# brakelight.net
KiCad netlist of a schematic drawn in EAGLE
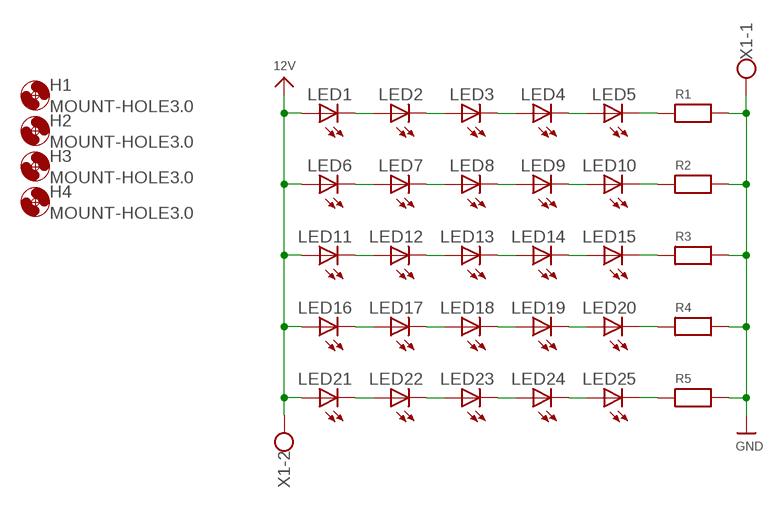
[diagram p0: schematic, sheet 1]

(export (version "E")
  (design (tool "Eeschema 10.0.6"))
  (components
    (comp (ref "H1")
      (value "MOUNT-HOLE3.0")
      (footprint "eagle-import:3,0")
      (libsource (lib "eagle-import") (part "MOUNT-HOLE3.0"))
    )
    (comp (ref "H2")
      (value "MOUNT-HOLE3.0")
      (footprint "eagle-import:3,0")
      (libsource (lib "eagle-import") (part "MOUNT-HOLE3.0"))
    )
    (comp (ref "H3")
      (value "MOUNT-HOLE3.0")
      (footprint "eagle-import:3,0")
      (libsource (lib "eagle-import") (part "MOUNT-HOLE3.0"))
    )
    (comp (ref "H4")
      (value "MOUNT-HOLE3.0")
      (footprint "eagle-import:3,0")
      (libsource (lib "eagle-import") (part "MOUNT-HOLE3.0"))
    )
    (comp (ref "LED1")
      (value "LEDP-LCC-2")
      (footprint "eagle-import:P-LCC-2")
      (libsource (lib "eagle-import") (part "LEDP-LCC-2"))
    )
    (comp (ref "LED2")
      (value "LEDP-LCC-2")
      (footprint "eagle-import:P-LCC-2")
      (libsource (lib "eagle-import") (part "LEDP-LCC-2"))
    )
    (comp (ref "LED3")
      (value "LEDP-LCC-2")
      (footprint "eagle-import:P-LCC-2")
      (libsource (lib "eagle-import") (part "LEDP-LCC-2"))
    )
    (comp (ref "LED4")
      (value "LEDP-LCC-2")
      (footprint "eagle-import:P-LCC-2")
      (libsource (lib "eagle-import") (part "LEDP-LCC-2"))
    )
    (comp (ref "LED5")
      (value "LEDP-LCC-2")
      (footprint "eagle-import:P-LCC-2")
      (libsource (lib "eagle-import") (part "LEDP-LCC-2"))
    )
    (comp (ref "LED6")
      (value "LEDP-LCC-2")
      (footprint "eagle-import:P-LCC-2")
      (libsource (lib "eagle-import") (part "LEDP-LCC-2"))
    )
    (comp (ref "LED7")
      (value "LEDP-LCC-2")
      (footprint "eagle-import:P-LCC-2")
      (libsource (lib "eagle-import") (part "LEDP-LCC-2"))
    )
    (comp (ref "LED8")
      (value "LEDP-LCC-2")
      (footprint "eagle-import:P-LCC-2")
      (libsource (lib "eagle-import") (part "LEDP-LCC-2"))
    )
    (comp (ref "LED9")
      (value "LEDP-LCC-2")
      (footprint "eagle-import:P-LCC-2")
      (libsource (lib "eagle-import") (part "LEDP-LCC-2"))
    )
    (comp (ref "LED10")
      (value "LEDP-LCC-2")
      (footprint "eagle-import:P-LCC-2")
      (libsource (lib "eagle-import") (part "LEDP-LCC-2"))
    )
    (comp (ref "LED11")
      (value "LEDP-LCC-2")
      (footprint "eagle-import:P-LCC-2")
      (libsource (lib "eagle-import") (part "LEDP-LCC-2"))
    )
    (comp (ref "LED12")
      (value "LEDP-LCC-2")
      (footprint "eagle-import:P-LCC-2")
      (libsource (lib "eagle-import") (part "LEDP-LCC-2"))
    )
    (comp (ref "LED13")
      (value "LEDP-LCC-2")
      (footprint "eagle-import:P-LCC-2")
      (libsource (lib "eagle-import") (part "LEDP-LCC-2"))
    )
    (comp (ref "LED14")
      (value "LEDP-LCC-2")
      (footprint "eagle-import:P-LCC-2")
      (libsource (lib "eagle-import") (part "LEDP-LCC-2"))
    )
    (comp (ref "LED15")
      (value "LEDP-LCC-2")
      (footprint "eagle-import:P-LCC-2")
      (libsource (lib "eagle-import") (part "LEDP-LCC-2"))
    )
    (comp (ref "LED16")
      (value "LEDP-LCC-2")
      (footprint "eagle-import:P-LCC-2")
      (libsource (lib "eagle-import") (part "LEDP-LCC-2"))
    )
    (comp (ref "LED17")
      (value "LEDP-LCC-2")
      (footprint "eagle-import:P-LCC-2")
      (libsource (lib "eagle-import") (part "LEDP-LCC-2"))
    )
    (comp (ref "LED18")
      (value "LEDP-LCC-2")
      (footprint "eagle-import:P-LCC-2")
      (libsource (lib "eagle-import") (part "LEDP-LCC-2"))
    )
    (comp (ref "LED19")
      (value "LEDP-LCC-2")
      (footprint "eagle-import:P-LCC-2")
      (libsource (lib "eagle-import") (part "LEDP-LCC-2"))
    )
    (comp (ref "LED20")
      (value "LEDP-LCC-2")
      (footprint "eagle-import:P-LCC-2")
      (libsource (lib "eagle-import") (part "LEDP-LCC-2"))
    )
    (comp (ref "LED21")
      (value "LEDP-LCC-2")
      (footprint "eagle-import:P-LCC-2")
      (libsource (lib "eagle-import") (part "LEDP-LCC-2"))
    )
    (comp (ref "LED22")
      (value "LEDP-LCC-2")
      (footprint "eagle-import:P-LCC-2")
      (libsource (lib "eagle-import") (part "LEDP-LCC-2"))
    )
    (comp (ref "LED23")
      (value "LEDP-LCC-2")
      (footprint "eagle-import:P-LCC-2")
      (libsource (lib "eagle-import") (part "LEDP-LCC-2"))
    )
    (comp (ref "LED24")
      (value "LEDP-LCC-2")
      (footprint "eagle-import:P-LCC-2")
      (libsource (lib "eagle-import") (part "LEDP-LCC-2"))
    )
    (comp (ref "LED25")
      (value "LEDP-LCC-2")
      (footprint "eagle-import:P-LCC-2")
      (libsource (lib "eagle-import") (part "LEDP-LCC-2"))
    )
    (comp (ref "R1")
      (value "RESISTOR0805")
      (footprint "eagle-import:0805")
      (libsource (lib "eagle-import") (part "RESISTOR0805"))
    )
    (comp (ref "R2")
      (value "RESISTOR0805")
      (footprint "eagle-import:0805")
      (libsource (lib "eagle-import") (part "RESISTOR0805"))
    )
    (comp (ref "R3")
      (value "RESISTOR0805")
      (footprint "eagle-import:0805")
      (libsource (lib "eagle-import") (part "RESISTOR0805"))
    )
    (comp (ref "R4")
      (value "RESISTOR0805")
      (footprint "eagle-import:0805")
      (libsource (lib "eagle-import") (part "RESISTOR0805"))
    )
    (comp (ref "R5")
      (value "RESISTOR0805")
      (footprint "eagle-import:0805")
      (libsource (lib "eagle-import") (part "RESISTOR0805"))
    )
    (comp (ref "X1")
      (value "W237-102")
      (footprint "eagle-import:W237-102")
      (fields (field (name "MPN") "237-102"))
      (libsource (lib "eagle-import") (part "W237-102"))
    )
  )
  (nets
    (net (code "1") (name "12V") (class "Default")
      (node (ref "LED1") (pin "A") (pinfunction "A_A") (pintype "passive"))
      (node (ref "LED11") (pin "A") (pinfunction "A_A") (pintype "passive"))
      (node (ref "LED16") (pin "A") (pinfunction "A_A") (pintype "passive"))
      (node (ref "LED21") (pin "A") (pinfunction "A_A") (pintype "passive"))
      (node (ref "LED6") (pin "A") (pinfunction "A_A") (pintype "passive"))
      (node (ref "X1") (pin "2") (pinfunction "KL_2") (pintype "passive"))
    )
    (net (code "2") (name "GND") (class "Default")
      (node (ref "R1") (pin "2") (pinfunction "2_2") (pintype "passive"))
      (node (ref "R2") (pin "2") (pinfunction "2_2") (pintype "passive"))
      (node (ref "R3") (pin "2") (pinfunction "2_2") (pintype "passive"))
      (node (ref "R4") (pin "2") (pinfunction "2_2") (pintype "passive"))
      (node (ref "R5") (pin "2") (pinfunction "2_2") (pintype "passive"))
      (node (ref "X1") (pin "1") (pinfunction "KL_1") (pintype "passive"))
    )
    (net (code "3") (name "Net-(LED1-PadC)") (class "Default")
      (node (ref "LED1") (pin "C") (pinfunction "C_C") (pintype "passive"))
      (node (ref "LED2") (pin "A") (pinfunction "A_A") (pintype "passive"))
    )
    (net (code "4") (name "Net-(LED2-PadC)") (class "Default")
      (node (ref "LED2") (pin "C") (pinfunction "C_C") (pintype "passive"))
      (node (ref "LED3") (pin "A") (pinfunction "A_A") (pintype "passive"))
    )
    (net (code "5") (name "Net-(LED3-PadC)") (class "Default")
      (node (ref "LED3") (pin "C") (pinfunction "C_C") (pintype "passive"))
      (node (ref "LED4") (pin "A") (pinfunction "A_A") (pintype "passive"))
    )
    (net (code "6") (name "Net-(LED4-PadC)") (class "Default")
      (node (ref "LED4") (pin "C") (pinfunction "C_C") (pintype "passive"))
      (node (ref "LED5") (pin "A") (pinfunction "A_A") (pintype "passive"))
    )
    (net (code "7") (name "Net-(LED5-PadC)") (class "Default")
      (node (ref "LED5") (pin "C") (pinfunction "C_C") (pintype "passive"))
      (node (ref "R1") (pin "1") (pinfunction "1_1") (pintype "passive"))
    )
    (net (code "8") (name "Net-(LED6-PadC)") (class "Default")
      (node (ref "LED6") (pin "C") (pinfunction "C_C") (pintype "passive"))
      (node (ref "LED7") (pin "A") (pinfunction "A_A") (pintype "passive"))
    )
    (net (code "9") (name "Net-(LED7-PadC)") (class "Default")
      (node (ref "LED7") (pin "C") (pinfunction "C_C") (pintype "passive"))
      (node (ref "LED8") (pin "A") (pinfunction "A_A") (pintype "passive"))
    )
    (net (code "10") (name "Net-(LED8-PadC)") (class "Default")
      (node (ref "LED8") (pin "C") (pinfunction "C_C") (pintype "passive"))
      (node (ref "LED9") (pin "A") (pinfunction "A_A") (pintype "passive"))
    )
    (net (code "11") (name "Net-(LED10-PadA)") (class "Default")
      (node (ref "LED10") (pin "A") (pinfunction "A_A") (pintype "passive"))
      (node (ref "LED9") (pin "C") (pinfunction "C_C") (pintype "passive"))
    )
    (net (code "12") (name "Net-(LED10-PadC)") (class "Default")
      (node (ref "LED10") (pin "C") (pinfunction "C_C") (pintype "passive"))
      (node (ref "R2") (pin "1") (pinfunction "1_1") (pintype "passive"))
    )
    (net (code "13") (name "Net-(LED11-PadC)") (class "Default")
      (node (ref "LED11") (pin "C") (pinfunction "C_C") (pintype "passive"))
      (node (ref "LED12") (pin "A") (pinfunction "A_A") (pintype "passive"))
    )
    (net (code "14") (name "Net-(LED12-PadC)") (class "Default")
      (node (ref "LED12") (pin "C") (pinfunction "C_C") (pintype "passive"))
      (node (ref "LED13") (pin "A") (pinfunction "A_A") (pintype "passive"))
    )
    (net (code "15") (name "Net-(LED13-PadC)") (class "Default")
      (node (ref "LED13") (pin "C") (pinfunction "C_C") (pintype "passive"))
      (node (ref "LED14") (pin "A") (pinfunction "A_A") (pintype "passive"))
    )
    (net (code "16") (name "Net-(LED14-PadC)") (class "Default")
      (node (ref "LED14") (pin "C") (pinfunction "C_C") (pintype "passive"))
      (node (ref "LED15") (pin "A") (pinfunction "A_A") (pintype "passive"))
    )
    (net (code "17") (name "Net-(LED15-PadC)") (class "Default")
      (node (ref "LED15") (pin "C") (pinfunction "C_C") (pintype "passive"))
      (node (ref "R3") (pin "1") (pinfunction "1_1") (pintype "passive"))
    )
    (net (code "18") (name "Net-(LED16-PadC)") (class "Default")
      (node (ref "LED16") (pin "C") (pinfunction "C_C") (pintype "passive"))
      (node (ref "LED17") (pin "A") (pinfunction "A_A") (pintype "passive"))
    )
    (net (code "19") (name "Net-(LED17-PadC)") (class "Default")
      (node (ref "LED17") (pin "C") (pinfunction "C_C") (pintype "passive"))
      (node (ref "LED18") (pin "A") (pinfunction "A_A") (pintype "passive"))
    )
    (net (code "20") (name "Net-(LED18-PadC)") (class "Default")
      (node (ref "LED18") (pin "C") (pinfunction "C_C") (pintype "passive"))
      (node (ref "LED19") (pin "A") (pinfunction "A_A") (pintype "passive"))
    )
    (net (code "21") (name "Net-(LED19-PadC)") (class "Default")
      (node (ref "LED19") (pin "C") (pinfunction "C_C") (pintype "passive"))
      (node (ref "LED20") (pin "A") (pinfunction "A_A") (pintype "passive"))
    )
    (net (code "22") (name "Net-(LED20-PadC)") (class "Default")
      (node (ref "LED20") (pin "C") (pinfunction "C_C") (pintype "passive"))
      (node (ref "R4") (pin "1") (pinfunction "1_1") (pintype "passive"))
    )
    (net (code "23") (name "Net-(LED21-PadC)") (class "Default")
      (node (ref "LED21") (pin "C") (pinfunction "C_C") (pintype "passive"))
      (node (ref "LED22") (pin "A") (pinfunction "A_A") (pintype "passive"))
    )
    (net (code "24") (name "Net-(LED22-PadC)") (class "Default")
      (node (ref "LED22") (pin "C") (pinfunction "C_C") (pintype "passive"))
      (node (ref "LED23") (pin "A") (pinfunction "A_A") (pintype "passive"))
    )
    (net (code "25") (name "Net-(LED23-PadC)") (class "Default")
      (node (ref "LED23") (pin "C") (pinfunction "C_C") (pintype "passive"))
      (node (ref "LED24") (pin "A") (pinfunction "A_A") (pintype "passive"))
    )
    (net (code "26") (name "Net-(LED24-PadC)") (class "Default")
      (node (ref "LED24") (pin "C") (pinfunction "C_C") (pintype "passive"))
      (node (ref "LED25") (pin "A") (pinfunction "A_A") (pintype "passive"))
    )
    (net (code "27") (name "Net-(LED25-PadC)") (class "Default")
      (node (ref "LED25") (pin "C") (pinfunction "C_C") (pintype "passive"))
      (node (ref "R5") (pin "1") (pinfunction "1_1") (pintype "passive"))
    )
  )
)
